# VCLFO_th_2.net
KiCad netlist of a schematic drawn in EAGLE
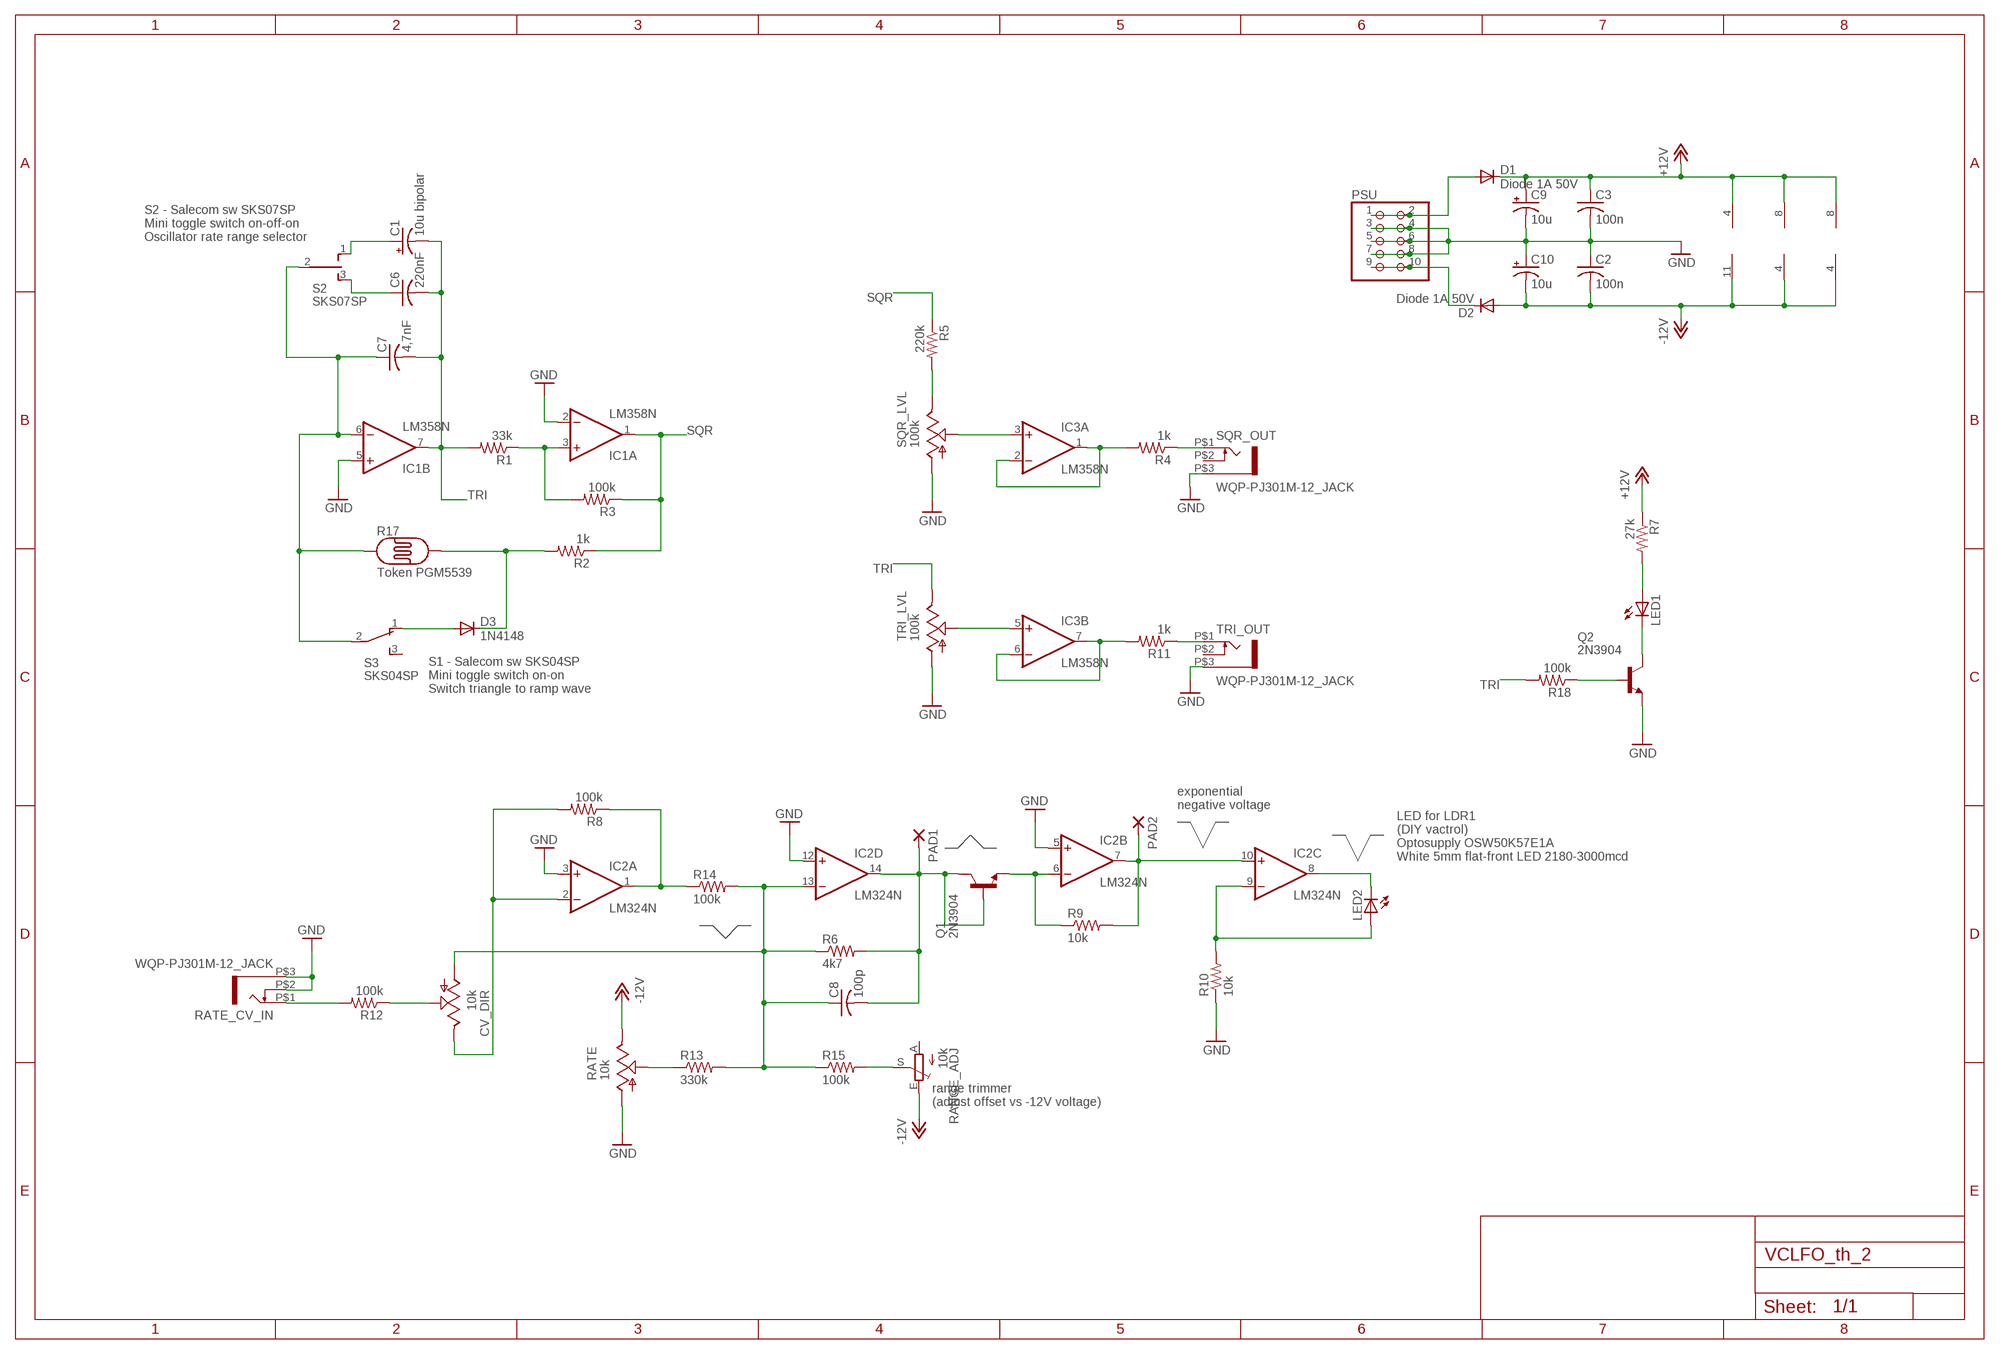
[diagram p0: schematic, sheet 1]

(export (version "E")
  (design (tool "Eeschema 10.0.6"))
  (components
    (comp (ref "C1")
      (value "10u bipolar")
      (footprint "eagle-import:E2,5-5")
      (libsource (lib "eagle-import") (part "CPOL-USE2.5-5"))
    )
    (comp (ref "C2")
      (value "100n")
      (footprint "eagle-import:C025-025X050")
      (libsource (lib "eagle-import") (part "C-US025-025X050"))
    )
    (comp (ref "C3")
      (value "100n")
      (footprint "eagle-import:C025-025X050")
      (libsource (lib "eagle-import") (part "C-US025-025X050"))
    )
    (comp (ref "C6")
      (value "220nF")
      (footprint "eagle-import:C050-025X075")
      (libsource (lib "eagle-import") (part "C-US050-025X075"))
    )
    (comp (ref "C7")
      (value "4,7nF")
      (footprint "eagle-import:C025-025X050")
      (libsource (lib "eagle-import") (part "C-US025-025X050"))
    )
    (comp (ref "C8")
      (value "100p")
      (footprint "eagle-import:C025-025X050")
      (libsource (lib "eagle-import") (part "C-US025-025X050"))
    )
    (comp (ref "C9")
      (value "10u")
      (footprint "eagle-import:E2,5-5")
      (libsource (lib "eagle-import") (part "CPOL-USE2.5-5"))
    )
    (comp (ref "C10")
      (value "10u")
      (footprint "eagle-import:E2,5-5")
      (libsource (lib "eagle-import") (part "CPOL-USE2.5-5"))
    )
    (comp (ref "CV_DIR")
      (value "10k")
      (footprint "eagle-import:ALPS_POT_VERTICAL")
      (libsource (lib "eagle-import") (part "POT_USVERTICAL"))
    )
    (comp (ref "D1")
      (value "Diode 1A 50V")
      (footprint "eagle-import:D-2.5")
      (libsource (lib "eagle-import") (part "DIODE-D-2.5"))
    )
    (comp (ref "D2")
      (value "Diode 1A 50V")
      (footprint "eagle-import:D-2.5")
      (libsource (lib "eagle-import") (part "DIODE-D-2.5"))
    )
    (comp (ref "D3")
      (value "1N4148")
      (footprint "eagle-import:D-5")
      (libsource (lib "eagle-import") (part "DIODE-D-5"))
    )
    (comp (ref "IC1")
      (value "LM358N")
      (footprint "eagle-import:DIL08")
      (libsource (lib "eagle-import") (part "LM358N"))
    )
    (comp (ref "IC2")
      (value "LM324N")
      (footprint "eagle-import:DIL14")
      (libsource (lib "eagle-import") (part "LM324N"))
    )
    (comp (ref "IC3")
      (value "LM358N")
      (footprint "eagle-import:DIL08")
      (libsource (lib "eagle-import") (part "LM358N"))
    )
    (comp (ref "LED1")
      (value "LED5MM")
      (footprint "eagle-import:LED5MM")
      (libsource (lib "eagle-import") (part "LED5MM"))
    )
    (comp (ref "LED2")
      (value "LED5MM")
      (footprint "eagle-import:LED5MM")
      (libsource (lib "eagle-import") (part "LED5MM"))
    )
    (comp (ref "PAD1")
      (value "1,6/0,8")
      (footprint "eagle-import:1,6_0,8")
      (libsource (lib "eagle-import") (part "1,6/0,8"))
    )
    (comp (ref "PAD2")
      (value "1,6/0,8")
      (footprint "eagle-import:1,6_0,8")
      (libsource (lib "eagle-import") (part "1,6/0,8"))
    )
    (comp (ref "PSU")
      (value "PINHD-2X5")
      (footprint "eagle-import:2X05")
      (libsource (lib "eagle-import") (part "PINHD-2X5"))
    )
    (comp (ref "Q1")
      (value "2N3904")
      (footprint "eagle-import:TO92")
      (libsource (lib "eagle-import") (part "2N3904"))
    )
    (comp (ref "Q2")
      (value "2N3904")
      (footprint "eagle-import:TO92")
      (libsource (lib "eagle-import") (part "2N3904"))
    )
    (comp (ref "R1")
      (value "33k")
      (footprint "eagle-import:0204V")
      (libsource (lib "eagle-import") (part "R-US_0204/2V"))
    )
    (comp (ref "R2")
      (value "1k")
      (footprint "eagle-import:0204V")
      (libsource (lib "eagle-import") (part "R-US_0204/2V"))
    )
    (comp (ref "R3")
      (value "100k")
      (footprint "eagle-import:0204V")
      (libsource (lib "eagle-import") (part "R-US_0204/2V"))
    )
    (comp (ref "R4")
      (value "1k")
      (footprint "eagle-import:0204V")
      (libsource (lib "eagle-import") (part "R-US_0204/2V"))
    )
    (comp (ref "R5")
      (value "220k")
      (footprint "eagle-import:0204V")
      (libsource (lib "eagle-import") (part "R-US_0204/2V"))
    )
    (comp (ref "R6")
      (value "4k7")
      (footprint "eagle-import:0204V")
      (libsource (lib "eagle-import") (part "R-US_0204/2V"))
    )
    (comp (ref "R7")
      (value "27k")
      (footprint "eagle-import:0204V")
      (libsource (lib "eagle-import") (part "R-US_0204/2V"))
    )
    (comp (ref "R8")
      (value "100k")
      (footprint "eagle-import:0204V")
      (libsource (lib "eagle-import") (part "R-US_0204/2V"))
    )
    (comp (ref "R9")
      (value "10k")
      (footprint "eagle-import:0204V")
      (libsource (lib "eagle-import") (part "R-US_0204/2V"))
    )
    (comp (ref "R10")
      (value "10k")
      (footprint "eagle-import:0204V")
      (libsource (lib "eagle-import") (part "R-US_0204/2V"))
    )
    (comp (ref "R11")
      (value "1k")
      (footprint "eagle-import:0204V")
      (libsource (lib "eagle-import") (part "R-US_0204/2V"))
    )
    (comp (ref "R12")
      (value "100k")
      (footprint "eagle-import:0204V")
      (libsource (lib "eagle-import") (part "R-US_0204/2V"))
    )
    (comp (ref "R13")
      (value "330k")
      (footprint "eagle-import:0204V")
      (libsource (lib "eagle-import") (part "R-US_0204/2V"))
    )
    (comp (ref "R14")
      (value "100k")
      (footprint "eagle-import:0204V")
      (libsource (lib "eagle-import") (part "R-US_0204/2V"))
    )
    (comp (ref "R15")
      (value "100k")
      (footprint "eagle-import:0204V")
      (libsource (lib "eagle-import") (part "R-US_0204/2V"))
    )
    (comp (ref "R17")
      (value "Token PGM5539")
      (footprint "eagle-import:PHOTOCELL")
      (libsource (lib "eagle-import") (part "PHOTOCELLPTH"))
    )
    (comp (ref "R18")
      (value "100k")
      (footprint "eagle-import:0204V")
      (libsource (lib "eagle-import") (part "R-US_0204/2V"))
    )
    (comp (ref "RANGE_ADJ")
      (value "10k")
      (footprint "eagle-import:B25P")
      (libsource (lib "eagle-import") (part "TRIM_EU-B25P"))
    )
    (comp (ref "RATE")
      (value "10k")
      (footprint "eagle-import:ALPS_POT_VERTICAL")
      (libsource (lib "eagle-import") (part "POT_USVERTICAL"))
    )
    (comp (ref "RATE_CV_IN")
      (value "WQP-PJ301M-12_JACK")
      (footprint "eagle-import:WQP-PJ301M-12_JACK")
      (libsource (lib "eagle-import") (part "WQP-PJ301M-12_JACK"))
    )
    (comp (ref "S2")
      (value "SKS07SP")
      (footprint "eagle-import:TL3XPO")
      (libsource (lib "eagle-import") (part "TL39PO"))
    )
    (comp (ref "S3")
      (value "SKS04SP")
      (footprint "eagle-import:TL3XPO")
      (libsource (lib "eagle-import") (part "TL36PO"))
    )
    (comp (ref "SQR_LVL")
      (value "100k")
      (footprint "eagle-import:ALPS_POT_VERTICAL")
      (libsource (lib "eagle-import") (part "POT_USVERTICAL"))
    )
    (comp (ref "SQR_OUT")
      (value "WQP-PJ301M-12_JACK")
      (footprint "eagle-import:WQP-PJ301M-12_JACK")
      (libsource (lib "eagle-import") (part "WQP-PJ301M-12_JACK"))
    )
    (comp (ref "TRI_LVL")
      (value "100k")
      (footprint "eagle-import:ALPS_POT_VERTICAL")
      (libsource (lib "eagle-import") (part "POT_USVERTICAL"))
    )
    (comp (ref "TRI_OUT")
      (value "WQP-PJ301M-12_JACK")
      (footprint "eagle-import:WQP-PJ301M-12_JACK")
      (libsource (lib "eagle-import") (part "WQP-PJ301M-12_JACK"))
    )
  )
  (nets
    (net (code "1") (name "+12V") (class "Default")
      (node (ref "C3") (pin "1") (pinfunction "1_1") (pintype "passive"))
      (node (ref "C9") (pin "+") (pinfunction "+_+") (pintype "passive"))
      (node (ref "D1") (pin "C") (pinfunction "C_C") (pintype "passive"))
      (node (ref "IC1") (pin "8") (pinfunction "V+_8") (pintype "power_in"))
      (node (ref "IC2") (pin "4") (pinfunction "V+_4") (pintype "power_in"))
      (node (ref "IC3") (pin "8") (pinfunction "V+_8") (pintype "power_in"))
      (node (ref "R7") (pin "1") (pinfunction "1_1") (pintype "passive"))
    )
    (net (code "2") (name "-12V") (class "Default")
      (node (ref "C10") (pin "-") (pinfunction "-_-") (pintype "passive"))
      (node (ref "C2") (pin "2") (pinfunction "2_2") (pintype "passive"))
      (node (ref "D2") (pin "A") (pinfunction "A_A") (pintype "passive"))
      (node (ref "IC1") (pin "4") (pinfunction "V-_4") (pintype "power_in"))
      (node (ref "IC2") (pin "11") (pinfunction "V-_11") (pintype "power_in"))
      (node (ref "IC3") (pin "4") (pinfunction "V-_4") (pintype "power_in"))
      (node (ref "RANGE_ADJ") (pin "E") (pinfunction "E_E") (pintype "passive"))
      (node (ref "RATE") (pin "P$1") (pinfunction "E_P$1") (pintype "passive"))
    )
    (net (code "3") (name "/SQR") (class "Default")
      (node (ref "IC1") (pin "1") (pinfunction "OUT_1") (pintype "output"))
      (node (ref "R2") (pin "1") (pinfunction "1_1") (pintype "passive"))
      (node (ref "R3") (pin "1") (pinfunction "1_1") (pintype "passive"))
      (node (ref "R5") (pin "1") (pinfunction "1_1") (pintype "passive"))
    )
    (net (code "4") (name "/TRI") (class "Default")
      (node (ref "C1") (pin "-") (pinfunction "-_-") (pintype "passive"))
      (node (ref "C6") (pin "2") (pinfunction "2_2") (pintype "passive"))
      (node (ref "C7") (pin "2") (pinfunction "2_2") (pintype "passive"))
      (node (ref "IC1") (pin "7") (pinfunction "OUT_7") (pintype "output"))
      (node (ref "R1") (pin "2") (pinfunction "2_2") (pintype "passive"))
      (node (ref "R18") (pin "2") (pinfunction "2_2") (pintype "passive"))
      (node (ref "TRI_LVL") (pin "P$1") (pinfunction "E_P$1") (pintype "passive"))
    )
    (net (code "5") (name "GND") (class "Default")
      (node (ref "C10") (pin "+") (pinfunction "+_+") (pintype "passive"))
      (node (ref "C2") (pin "1") (pinfunction "1_1") (pintype "passive"))
      (node (ref "C3") (pin "2") (pinfunction "2_2") (pintype "passive"))
      (node (ref "C9") (pin "-") (pinfunction "-_-") (pintype "passive"))
      (node (ref "IC1") (pin "2") (pinfunction "-IN_2") (pintype "input"))
      (node (ref "IC1") (pin "5") (pinfunction "+IN_5") (pintype "input"))
      (node (ref "IC2") (pin "12") (pinfunction "+IN_12") (pintype "input"))
      (node (ref "IC2") (pin "3") (pinfunction "+IN_3") (pintype "input"))
      (node (ref "IC2") (pin "5") (pinfunction "+IN_5") (pintype "input"))
      (node (ref "PSU") (pin "3") (pinfunction "3_3") (pintype "passive"))
      (node (ref "PSU") (pin "4") (pinfunction "4_4") (pintype "passive"))
      (node (ref "PSU") (pin "5") (pinfunction "5_5") (pintype "passive"))
      (node (ref "PSU") (pin "6") (pinfunction "6_6") (pintype "passive"))
      (node (ref "PSU") (pin "7") (pinfunction "7_7") (pintype "passive"))
      (node (ref "PSU") (pin "8") (pinfunction "8_8") (pintype "passive"))
      (node (ref "Q2") (pin "3") (pinfunction "E_3") (pintype "passive"))
      (node (ref "R10") (pin "1") (pinfunction "1_1") (pintype "passive"))
      (node (ref "RATE") (pin "P$3") (pinfunction "A_P$3") (pintype "passive"))
      (node (ref "RATE_CV_IN") (pin "P$2") (pinfunction "3_P$2") (pintype "passive"))
      (node (ref "RATE_CV_IN") (pin "P$3") (pinfunction "1_P$3") (pintype "passive"))
      (node (ref "SQR_LVL") (pin "P$3") (pinfunction "A_P$3") (pintype "passive"))
      (node (ref "SQR_OUT") (pin "P$3") (pinfunction "1_P$3") (pintype "passive"))
      (node (ref "TRI_LVL") (pin "P$3") (pinfunction "A_P$3") (pintype "passive"))
      (node (ref "TRI_OUT") (pin "P$3") (pinfunction "1_P$3") (pintype "passive"))
    )
    (net (code "6") (name "Net-(CV_DIR-A)") (class "Default")
      (node (ref "C8") (pin "1") (pinfunction "1_1") (pintype "passive"))
      (node (ref "CV_DIR") (pin "P$3") (pinfunction "A_P$3") (pintype "passive"))
      (node (ref "IC2") (pin "13") (pinfunction "-IN_13") (pintype "input"))
      (node (ref "R13") (pin "2") (pinfunction "2_2") (pintype "passive"))
      (node (ref "R14") (pin "2") (pinfunction "2_2") (pintype "passive"))
      (node (ref "R15") (pin "1") (pinfunction "1_1") (pintype "passive"))
      (node (ref "R6") (pin "1") (pinfunction "1_1") (pintype "passive"))
    )
    (net (code "7") (name "Net-(CV_DIR-E)") (class "Default")
      (node (ref "CV_DIR") (pin "P$1") (pinfunction "E_P$1") (pintype "passive"))
      (node (ref "IC2") (pin "2") (pinfunction "-IN_2") (pintype "input"))
      (node (ref "R8") (pin "2") (pinfunction "2_2") (pintype "passive"))
    )
    (net (code "8") (name "Net-(CV_DIR-S)") (class "Default")
      (node (ref "CV_DIR") (pin "P$2") (pinfunction "S_P$2") (pintype "passive"))
      (node (ref "R12") (pin "1") (pinfunction "1_1") (pintype "passive"))
    )
    (net (code "9") (name "Net-(D1-PadA)") (class "Default")
      (node (ref "D1") (pin "A") (pinfunction "A_A") (pintype "passive"))
      (node (ref "PSU") (pin "1") (pinfunction "1_1") (pintype "passive"))
      (node (ref "PSU") (pin "2") (pinfunction "2_2") (pintype "passive"))
    )
    (net (code "10") (name "Net-(D2-PadC)") (class "Default")
      (node (ref "D2") (pin "C") (pinfunction "C_C") (pintype "passive"))
      (node (ref "PSU") (pin "10") (pinfunction "10_10") (pintype "passive"))
      (node (ref "PSU") (pin "9") (pinfunction "9_9") (pintype "passive"))
    )
    (net (code "11") (name "Net-(IC1A-+IN)") (class "Default")
      (node (ref "IC1") (pin "3") (pinfunction "+IN_3") (pintype "input"))
      (node (ref "R1") (pin "1") (pinfunction "1_1") (pintype "passive"))
      (node (ref "R3") (pin "2") (pinfunction "2_2") (pintype "passive"))
    )
    (net (code "12") (name "Net-(IC1B--IN)") (class "Default")
      (node (ref "C7") (pin "1") (pinfunction "1_1") (pintype "passive"))
      (node (ref "IC1") (pin "6") (pinfunction "-IN_6") (pintype "input"))
      (node (ref "R17") (pin "1") (pinfunction "P$1_1") (pintype "bidirectional"))
      (node (ref "S2") (pin "2") (pinfunction "P_2") (pintype "passive"))
      (node (ref "S3") (pin "2") (pinfunction "P_2") (pintype "passive"))
    )
    (net (code "13") (name "Net-(IC2A-OUT)") (class "Default")
      (node (ref "IC2") (pin "1") (pinfunction "OUT_1") (pintype "output"))
      (node (ref "R14") (pin "1") (pinfunction "1_1") (pintype "passive"))
      (node (ref "R8") (pin "1") (pinfunction "1_1") (pintype "passive"))
    )
    (net (code "14") (name "Net-(IC2B--IN)") (class "Default")
      (node (ref "IC2") (pin "6") (pinfunction "-IN_6") (pintype "input"))
      (node (ref "Q1") (pin "3") (pinfunction "E_3") (pintype "passive"))
      (node (ref "R9") (pin "1") (pinfunction "1_1") (pintype "passive"))
    )
    (net (code "15") (name "Net-(IC2B-OUT)") (class "Default")
      (node (ref "IC2") (pin "10") (pinfunction "+IN_10") (pintype "input"))
      (node (ref "IC2") (pin "7") (pinfunction "OUT_7") (pintype "output"))
      (node (ref "PAD2") (pin "1") (pinfunction "P_1") (pintype "passive"))
      (node (ref "R9") (pin "2") (pinfunction "2_2") (pintype "passive"))
    )
    (net (code "16") (name "Net-(IC2C--IN)") (class "Default")
      (node (ref "IC2") (pin "9") (pinfunction "-IN_9") (pintype "input"))
      (node (ref "LED2") (pin "A") (pinfunction "A_A") (pintype "passive"))
      (node (ref "R10") (pin "2") (pinfunction "2_2") (pintype "passive"))
    )
    (net (code "17") (name "Net-(IC2C-OUT)") (class "Default")
      (node (ref "IC2") (pin "8") (pinfunction "OUT_8") (pintype "output"))
      (node (ref "LED2") (pin "K") (pinfunction "C_K") (pintype "passive"))
    )
    (net (code "18") (name "Net-(IC2D-OUT)") (class "Default")
      (node (ref "C8") (pin "2") (pinfunction "2_2") (pintype "passive"))
      (node (ref "IC2") (pin "14") (pinfunction "OUT_14") (pintype "output"))
      (node (ref "PAD1") (pin "1") (pinfunction "P_1") (pintype "passive"))
      (node (ref "Q1") (pin "1") (pinfunction "C_1") (pintype "passive"))
      (node (ref "Q1") (pin "2") (pinfunction "B_2") (pintype "passive"))
      (node (ref "R6") (pin "2") (pinfunction "2_2") (pintype "passive"))
    )
    (net (code "19") (name "Net-(IC3A-+IN)") (class "Default")
      (node (ref "IC3") (pin "3") (pinfunction "+IN_3") (pintype "input"))
      (node (ref "SQR_LVL") (pin "P$2") (pinfunction "S_P$2") (pintype "passive"))
    )
    (net (code "20") (name "Net-(IC3A--IN)") (class "Default")
      (node (ref "IC3") (pin "1") (pinfunction "OUT_1") (pintype "output"))
      (node (ref "IC3") (pin "2") (pinfunction "-IN_2") (pintype "input"))
      (node (ref "R4") (pin "2") (pinfunction "2_2") (pintype "passive"))
    )
    (net (code "21") (name "Net-(IC3B-+IN)") (class "Default")
      (node (ref "IC3") (pin "5") (pinfunction "+IN_5") (pintype "input"))
      (node (ref "TRI_LVL") (pin "P$2") (pinfunction "S_P$2") (pintype "passive"))
    )
    (net (code "22") (name "Net-(IC3B--IN)") (class "Default")
      (node (ref "IC3") (pin "6") (pinfunction "-IN_6") (pintype "input"))
      (node (ref "IC3") (pin "7") (pinfunction "OUT_7") (pintype "output"))
      (node (ref "R11") (pin "2") (pinfunction "2_2") (pintype "passive"))
    )
    (net (code "23") (name "Net-(LED1-C)") (class "Default")
      (node (ref "LED1") (pin "K") (pinfunction "C_K") (pintype "passive"))
      (node (ref "Q2") (pin "1") (pinfunction "C_1") (pintype "passive"))
    )
    (net (code "24") (name "Net-(LED1-PadA)") (class "Default")
      (node (ref "LED1") (pin "A") (pinfunction "A_A") (pintype "passive"))
      (node (ref "R7") (pin "2") (pinfunction "2_2") (pintype "passive"))
    )
    (net (code "25") (name "Net-(Q2-B)") (class "Default")
      (node (ref "Q2") (pin "2") (pinfunction "B_2") (pintype "passive"))
      (node (ref "R18") (pin "1") (pinfunction "1_1") (pintype "passive"))
    )
    (net (code "26") (name "Net-(R15-Pad2)") (class "Default")
      (node (ref "R15") (pin "2") (pinfunction "2_2") (pintype "passive"))
      (node (ref "RANGE_ADJ") (pin "S") (pinfunction "S_S") (pintype "passive"))
    )
    (net (code "27") (name "Net-(R17-P$2)") (class "Default")
      (node (ref "D3") (pin "C") (pinfunction "C_C") (pintype "passive"))
      (node (ref "R17") (pin "2") (pinfunction "P$2_2") (pintype "bidirectional"))
      (node (ref "R2") (pin "2") (pinfunction "2_2") (pintype "passive"))
    )
    (net (code "28") (name "Net-(RATE-S)") (class "Default")
      (node (ref "R13") (pin "1") (pinfunction "1_1") (pintype "passive"))
      (node (ref "RATE") (pin "P$2") (pinfunction "S_P$2") (pintype "passive"))
    )
    (net (code "29") (name "Net-(RATE_CV_IN-2)") (class "Default")
      (node (ref "R12") (pin "2") (pinfunction "2_2") (pintype "passive"))
      (node (ref "RATE_CV_IN") (pin "P$1") (pinfunction "2_P$1") (pintype "passive"))
    )
    (net (code "30") (name "Net-(S2-O)") (class "Default")
      (node (ref "C1") (pin "+") (pinfunction "+_+") (pintype "passive"))
      (node (ref "S2") (pin "1") (pinfunction "O_1") (pintype "passive"))
    )
    (net (code "31") (name "Net-(S2-S)") (class "Default")
      (node (ref "C6") (pin "1") (pinfunction "1_1") (pintype "passive"))
      (node (ref "S2") (pin "3") (pinfunction "S_3") (pintype "passive"))
    )
    (net (code "32") (name "Net-(S3-O)") (class "Default")
      (node (ref "D3") (pin "A") (pinfunction "A_A") (pintype "passive"))
      (node (ref "S3") (pin "1") (pinfunction "O_1") (pintype "passive"))
    )
    (net (code "33") (name "Net-(SQR_LVL-E)") (class "Default")
      (node (ref "R5") (pin "2") (pinfunction "2_2") (pintype "passive"))
      (node (ref "SQR_LVL") (pin "P$1") (pinfunction "E_P$1") (pintype "passive"))
    )
    (net (code "34") (name "Net-(SQR_OUT-2)") (class "Default")
      (node (ref "R4") (pin "1") (pinfunction "1_1") (pintype "passive"))
      (node (ref "SQR_OUT") (pin "P$1") (pinfunction "2_P$1") (pintype "passive"))
    )
    (net (code "35") (name "Net-(TRI_OUT-2)") (class "Default")
      (node (ref "R11") (pin "1") (pinfunction "1_1") (pintype "passive"))
      (node (ref "TRI_OUT") (pin "P$1") (pinfunction "2_P$1") (pintype "passive"))
    )
    (net (code "36") (name "unconnected-(RANGE_ADJ-PadA)") (class "Default")
      (node (ref "RANGE_ADJ") (pin "A") (pinfunction "A_A") (pintype "passive"))
    )
    (net (code "37") (name "unconnected-(S3-S-Pad3)") (class "Default")
      (node (ref "S3") (pin "3") (pinfunction "S_3") (pintype "passive"))
    )
    (net (code "38") (name "unconnected-(SQR_OUT-3-PadP$2)") (class "Default")
      (node (ref "SQR_OUT") (pin "P$2") (pinfunction "3_P$2") (pintype "passive"))
    )
    (net (code "39") (name "unconnected-(TRI_OUT-3-PadP$2)") (class "Default")
      (node (ref "TRI_OUT") (pin "P$2") (pinfunction "3_P$2") (pintype "passive"))
    )
  )
)
